# PIR_MOC_2.net
KiCad netlist of a schematic drawn in EAGLE
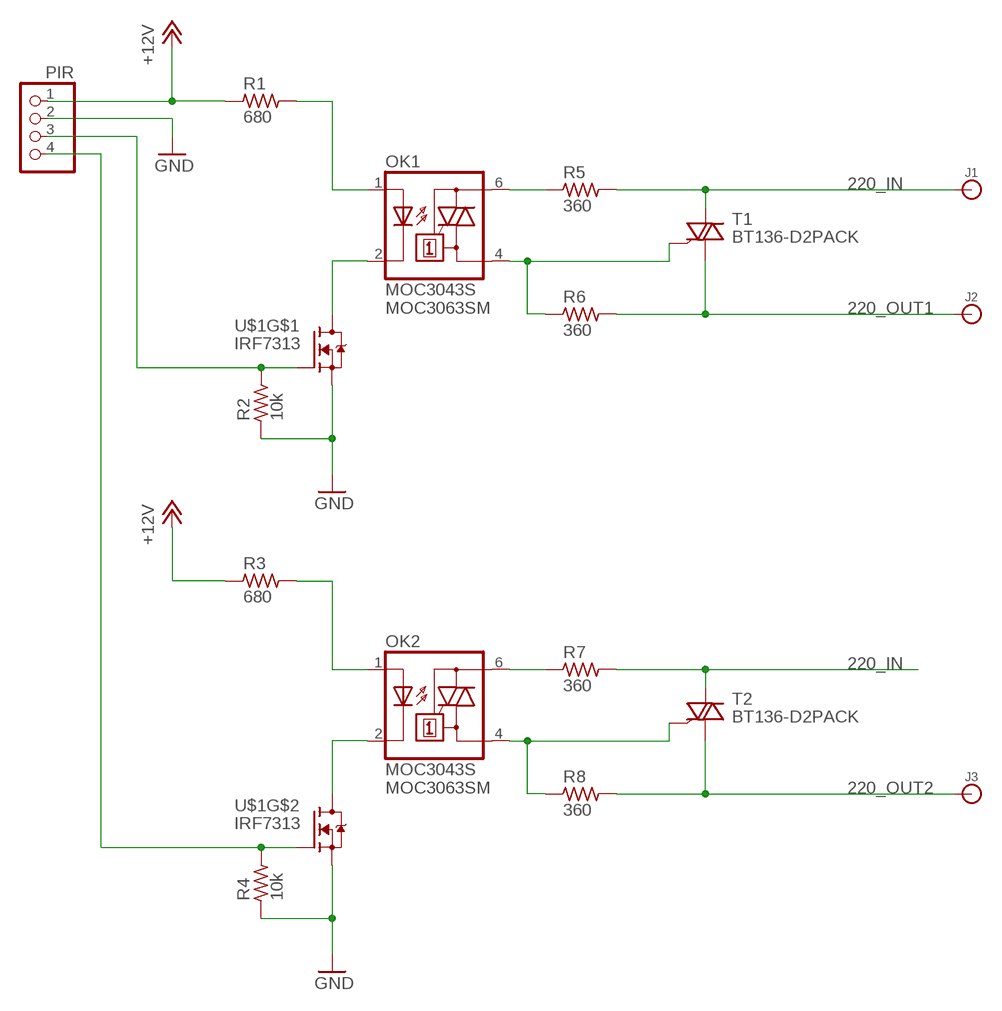
[diagram p0: schematic, sheet 1]

(export (version "E")
  (design (tool "Eeschema 10.0.6"))
  (components
    (comp (ref "J1")
      (value "BANANA_CONN")
      (footprint "eagle-import:BANANA_CONN")
      (libsource (lib "eagle-import") (part "BANANA_CONN"))
    )
    (comp (ref "J2")
      (value "BANANA_CONN")
      (footprint "eagle-import:BANANA_CONN")
      (libsource (lib "eagle-import") (part "BANANA_CONN"))
    )
    (comp (ref "J3")
      (value "BANANA_CONN")
      (footprint "eagle-import:BANANA_CONN")
      (libsource (lib "eagle-import") (part "BANANA_CONN"))
    )
    (comp (ref "OK1")
      (value "MOC3043S")
      (footprint "eagle-import:DIL6-SMD")
      (fields
        (field (name "MF") "FAIRCHILD SEMICONDUCTOR")
        (field (name "MPN") "MOC3043SM")
        (field (name "MPN_1") "MOC3063SM")
      )
      (libsource (lib "eagle-import") (part "MOC30S43"))
    )
    (comp (ref "OK2")
      (value "MOC3043S")
      (footprint "eagle-import:DIL6-SMD")
      (fields
        (field (name "MF") "FAIRCHILD SEMICONDUCTOR")
        (field (name "MPN") "MOC3043SM")
        (field (name "MPN_1") "MOC3063SM")
      )
      (libsource (lib "eagle-import") (part "MOC30S43"))
    )
    (comp (ref "PIR")
      (value "PINHD-1X04_2.54-S")
      (footprint "eagle-import:1X04-S")
      (libsource (lib "eagle-import") (part "PINHD-1X04_2.54-S"))
    )
    (comp (ref "R1")
      (value "680")
      (footprint "eagle-import:R1206")
      (libsource (lib "eagle-import") (part "R_1206"))
    )
    (comp (ref "R2")
      (value "10k")
      (footprint "eagle-import:R1206")
      (libsource (lib "eagle-import") (part "R_1206"))
    )
    (comp (ref "R3")
      (value "680")
      (footprint "eagle-import:R1206")
      (libsource (lib "eagle-import") (part "R_1206"))
    )
    (comp (ref "R4")
      (value "10k")
      (footprint "eagle-import:R1206")
      (libsource (lib "eagle-import") (part "R_1206"))
    )
    (comp (ref "R5")
      (value "360")
      (footprint "eagle-import:R1206")
      (libsource (lib "eagle-import") (part "R_1206"))
    )
    (comp (ref "R6")
      (value "360")
      (footprint "eagle-import:R1206")
      (libsource (lib "eagle-import") (part "R_1206"))
    )
    (comp (ref "R7")
      (value "360")
      (footprint "eagle-import:R1206")
      (libsource (lib "eagle-import") (part "R_1206"))
    )
    (comp (ref "R8")
      (value "360")
      (footprint "eagle-import:R1206")
      (libsource (lib "eagle-import") (part "R_1206"))
    )
    (comp (ref "T1")
      (value "BT136-D2PACK")
      (footprint "eagle-import:TO263")
      (libsource (lib "eagle-import") (part "BT136-D2PACK"))
    )
    (comp (ref "T2")
      (value "BT136-D2PACK")
      (footprint "eagle-import:TO263")
      (libsource (lib "eagle-import") (part "BT136-D2PACK"))
    )
    (comp (ref "U$1")
      (value "IRF7313")
      (footprint "eagle-import:SO-8")
      (libsource (lib "eagle-import") (part "IRF7313"))
    )
  )
  (nets
    (net (code "1") (name "+12V") (class "Default")
      (node (ref "PIR") (pin "1") (pinfunction "1_1") (pintype "passive"))
      (node (ref "R1") (pin "1") (pinfunction "1_1") (pintype "passive"))
      (node (ref "R3") (pin "1") (pinfunction "1_1") (pintype "passive"))
    )
    (net (code "2") (name "/220_IN") (class "Default")
      (node (ref "J1") (pin "P$1") (pinfunction "1_P$1") (pintype "passive"))
      (node (ref "R5") (pin "2") (pinfunction "2_2") (pintype "passive"))
      (node (ref "R7") (pin "2") (pinfunction "2_2") (pintype "passive"))
      (node (ref "T1") (pin "3") (pinfunction "A2_3") (pintype "passive"))
      (node (ref "T2") (pin "3") (pinfunction "A2_3") (pintype "passive"))
    )
    (net (code "3") (name "/220_OUT1") (class "Default")
      (node (ref "J2") (pin "P$1") (pinfunction "1_P$1") (pintype "passive"))
      (node (ref "R6") (pin "2") (pinfunction "2_2") (pintype "passive"))
      (node (ref "T1") (pin "1") (pinfunction "A1_1") (pintype "passive"))
    )
    (net (code "4") (name "/220_OUT2") (class "Default")
      (node (ref "J3") (pin "P$1") (pinfunction "1_P$1") (pintype "passive"))
      (node (ref "R8") (pin "2") (pinfunction "2_2") (pintype "passive"))
      (node (ref "T2") (pin "1") (pinfunction "A1_1") (pintype "passive"))
    )
    (net (code "5") (name "GND") (class "Default")
      (node (ref "PIR") (pin "2") (pinfunction "2_2") (pintype "passive"))
      (node (ref "R2") (pin "1") (pinfunction "1_1") (pintype "passive"))
      (node (ref "R4") (pin "1") (pinfunction "1_1") (pintype "passive"))
      (node (ref "U$1") (pin "1") (pinfunction "S_1") (pintype "passive"))
      (node (ref "U$1") (pin "3") (pinfunction "S_3") (pintype "passive"))
    )
    (net (code "6") (name "Net-(OK1-A)") (class "Default")
      (node (ref "OK1") (pin "1") (pinfunction "A_1") (pintype "passive"))
      (node (ref "R1") (pin "2") (pinfunction "2_2") (pintype "passive"))
    )
    (net (code "7") (name "Net-(OK1-A1)") (class "Default")
      (node (ref "OK1") (pin "4") (pinfunction "A1_4") (pintype "passive"))
      (node (ref "R6") (pin "1") (pinfunction "1_1") (pintype "passive"))
      (node (ref "T1") (pin "2") (pinfunction "G_2") (pintype "passive"))
    )
    (net (code "8") (name "Net-(OK1-A2)") (class "Default")
      (node (ref "OK1") (pin "6") (pinfunction "A2_6") (pintype "passive"))
      (node (ref "R5") (pin "1") (pinfunction "1_1") (pintype "passive"))
    )
    (net (code "9") (name "Net-(OK1-C)") (class "Default")
      (node (ref "OK1") (pin "2") (pinfunction "C_2") (pintype "passive"))
      (node (ref "U$1") (pin "7") (pinfunction "D_7") (pintype "passive"))
      (node (ref "U$1") (pin "8") (pinfunction "D_8") (pintype "passive"))
    )
    (net (code "10") (name "Net-(OK2-A)") (class "Default")
      (node (ref "OK2") (pin "1") (pinfunction "A_1") (pintype "passive"))
      (node (ref "R3") (pin "2") (pinfunction "2_2") (pintype "passive"))
    )
    (net (code "11") (name "Net-(OK2-A1)") (class "Default")
      (node (ref "OK2") (pin "4") (pinfunction "A1_4") (pintype "passive"))
      (node (ref "R8") (pin "1") (pinfunction "1_1") (pintype "passive"))
      (node (ref "T2") (pin "2") (pinfunction "G_2") (pintype "passive"))
    )
    (net (code "12") (name "Net-(OK2-A2)") (class "Default")
      (node (ref "OK2") (pin "6") (pinfunction "A2_6") (pintype "passive"))
      (node (ref "R7") (pin "1") (pinfunction "1_1") (pintype "passive"))
    )
    (net (code "13") (name "Net-(OK2-C)") (class "Default")
      (node (ref "OK2") (pin "2") (pinfunction "C_2") (pintype "passive"))
      (node (ref "U$1") (pin "5") (pinfunction "D_5") (pintype "passive"))
      (node (ref "U$1") (pin "6") (pinfunction "D_6") (pintype "passive"))
    )
    (net (code "14") (name "Net-(U$1A-G)") (class "Default")
      (node (ref "PIR") (pin "3") (pinfunction "3_3") (pintype "passive"))
      (node (ref "R2") (pin "2") (pinfunction "2_2") (pintype "passive"))
      (node (ref "U$1") (pin "2") (pinfunction "G_2") (pintype "passive"))
    )
    (net (code "15") (name "Net-(U$1B-G)") (class "Default")
      (node (ref "PIR") (pin "4") (pinfunction "4_4") (pintype "passive"))
      (node (ref "R4") (pin "2") (pinfunction "2_2") (pintype "passive"))
      (node (ref "U$1") (pin "4") (pinfunction "G_4") (pintype "passive"))
    )
  )
)
